# SCH_Type-c-Hub_2024-10-24.net
KiCad netlist of a schematic drawn in EasyEDA
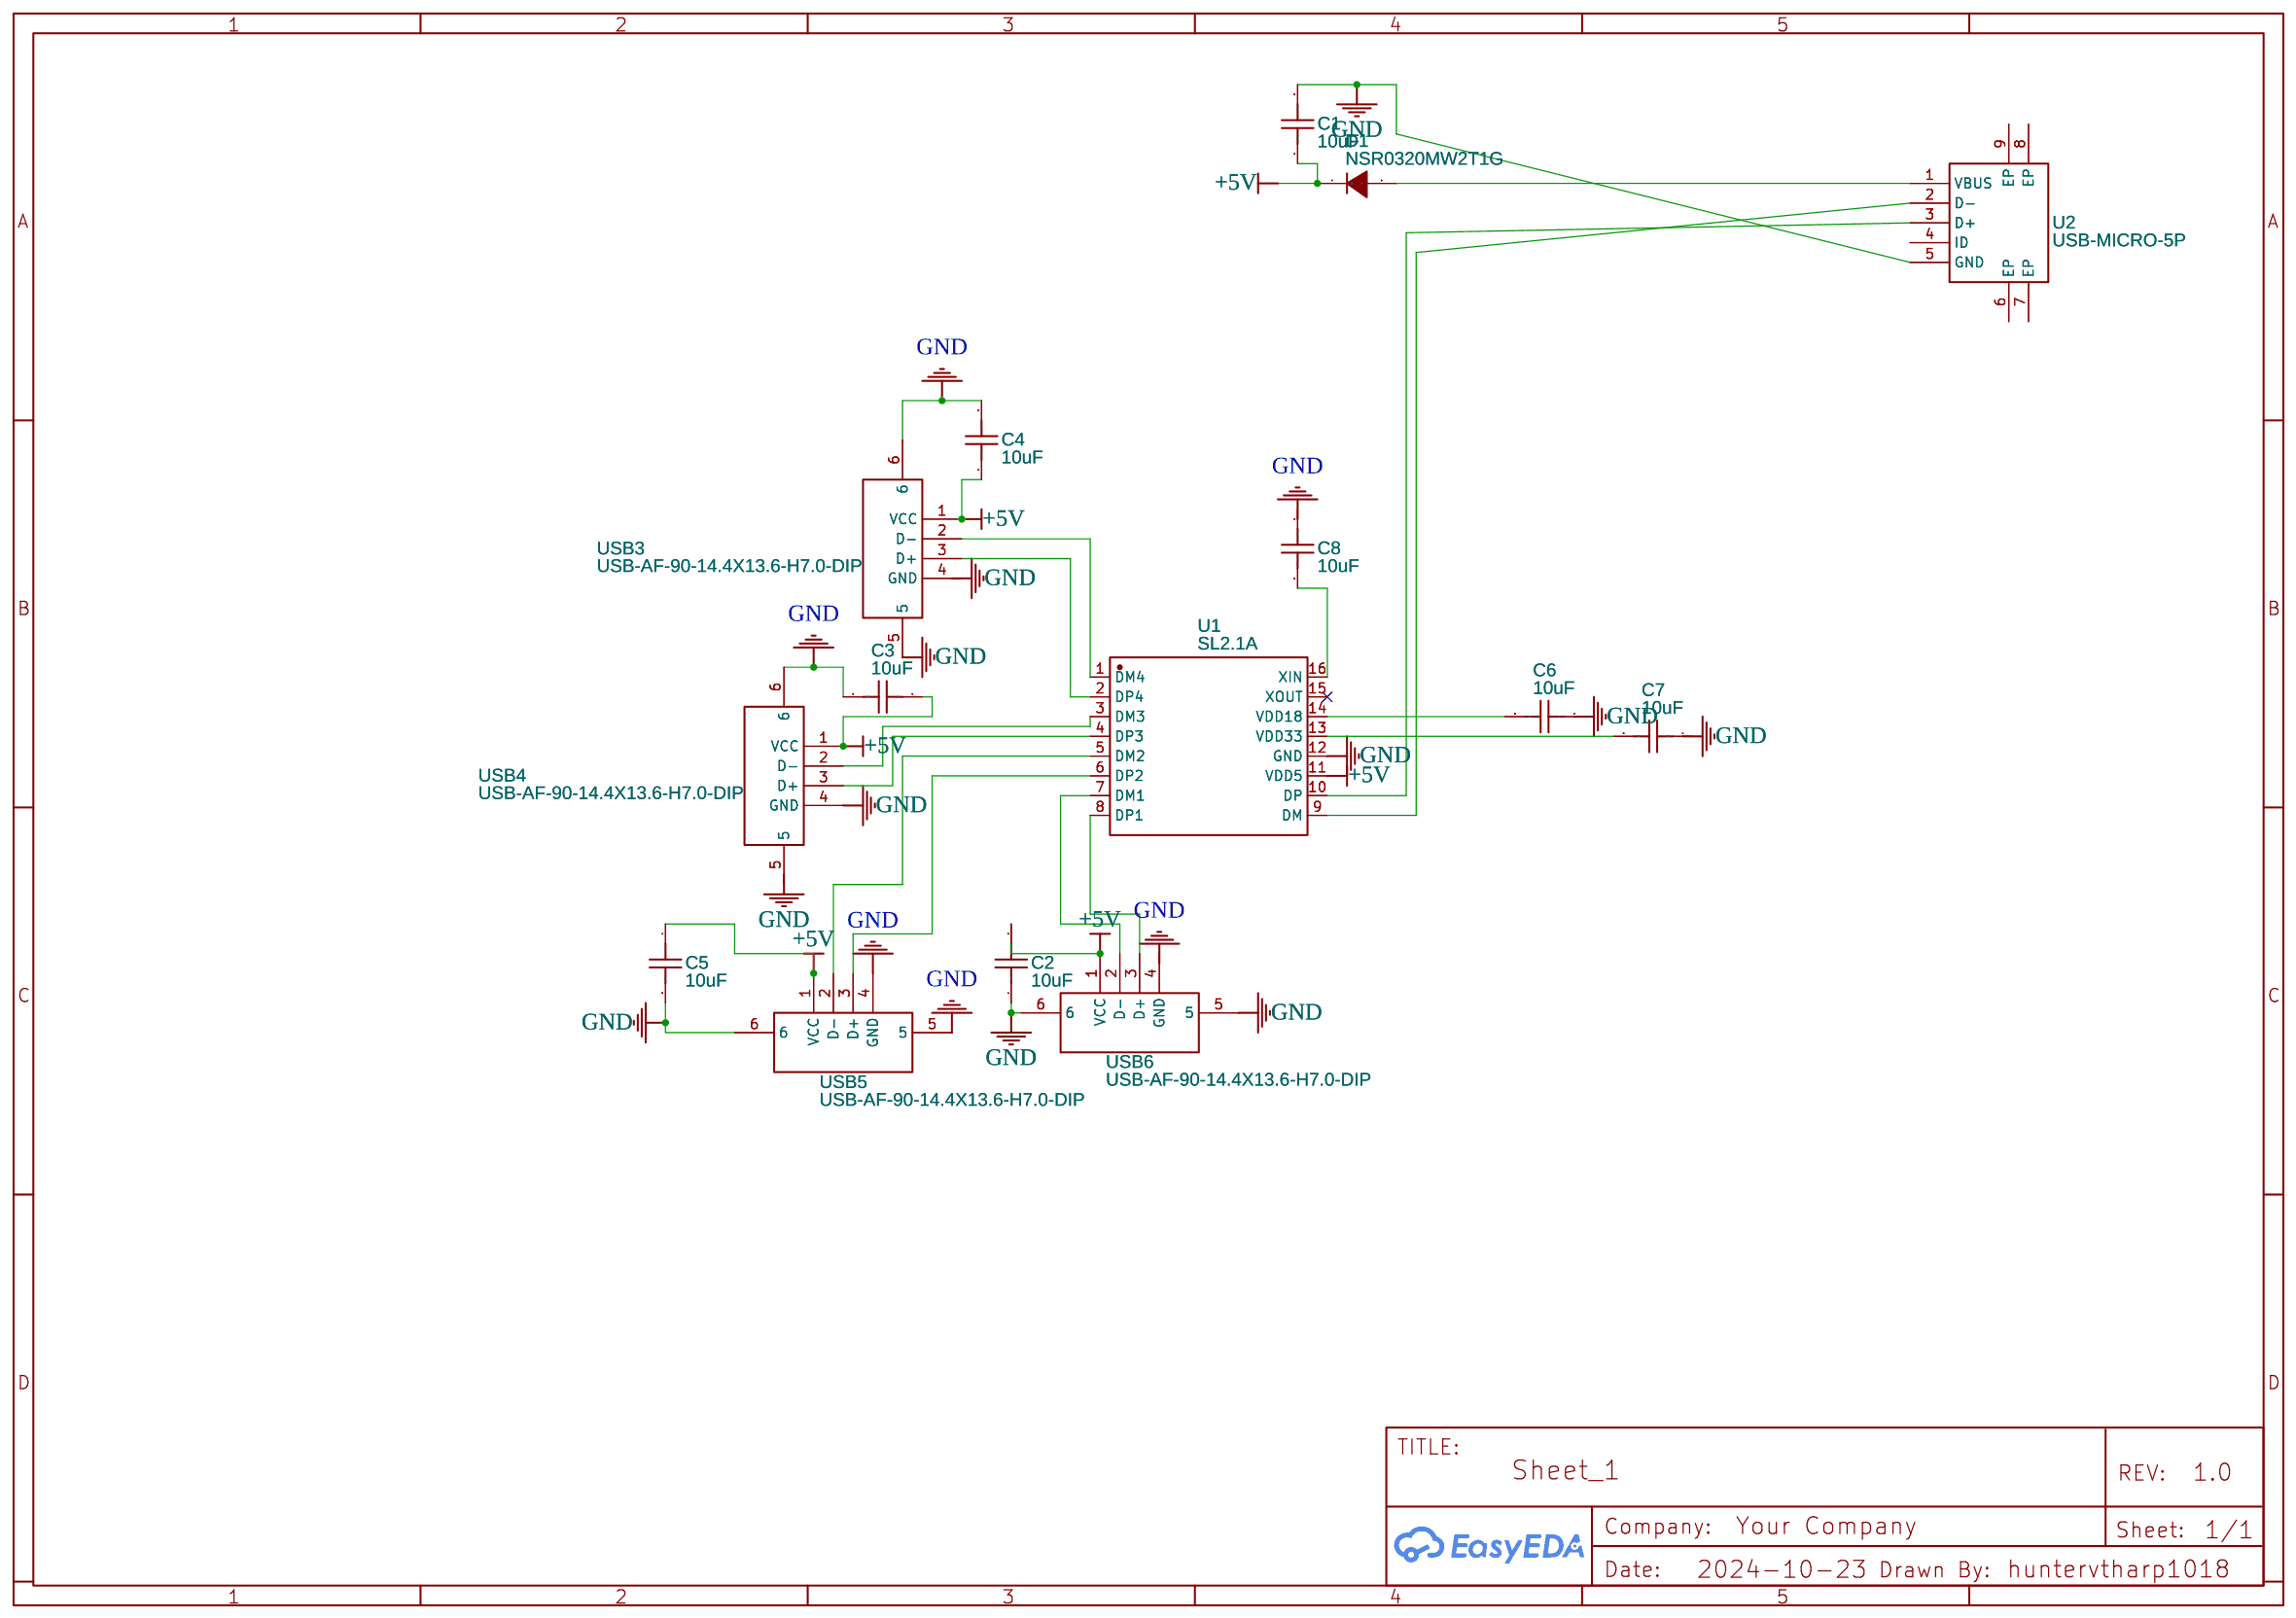
[diagram p0: schematic sheet]

(export (version "E")
  (design (tool "Eeschema 10.0.6"))
  (components
    (comp (ref "C1")
      (value "10uF")
      (fields
        (field (name "Manufacturer Part") "CL10A106KP8NNNC")
        (field (name "Manufacturer") "SAMSUNG(三星)")
      )
      (libsource (lib "") (part "CL10A106KP8NNNC_1"))
    )
    (comp (ref "C2")
      (value "10uF")
      (fields
        (field (name "Manufacturer Part") "CL10A106KP8NNNC")
        (field (name "Manufacturer") "SAMSUNG(三星)")
      )
      (libsource (lib "") (part "CL10A106KP8NNNC_1"))
    )
    (comp (ref "C3")
      (value "10uF")
      (fields
        (field (name "Manufacturer Part") "CL10A106KP8NNNC")
        (field (name "Manufacturer") "SAMSUNG(三星)")
      )
      (libsource (lib "") (part "CL10A106KP8NNNC_2"))
    )
    (comp (ref "C4")
      (value "10uF")
      (fields
        (field (name "Manufacturer Part") "CL10A106KP8NNNC")
        (field (name "Manufacturer") "SAMSUNG(三星)")
      )
      (libsource (lib "") (part "CL10A106KP8NNNC_1"))
    )
    (comp (ref "C5")
      (value "10uF")
      (fields
        (field (name "Manufacturer Part") "CL10A106KP8NNNC")
        (field (name "Manufacturer") "SAMSUNG(三星)")
      )
      (libsource (lib "") (part "CL10A106KP8NNNC"))
    )
    (comp (ref "C6")
      (value "10uF")
      (fields
        (field (name "Manufacturer Part") "CL10A106KP8NNNC")
        (field (name "Manufacturer") "SAMSUNG(三星)")
      )
      (libsource (lib "") (part "CL10A106KP8NNNC_2"))
    )
    (comp (ref "C7")
      (value "10uF")
      (fields
        (field (name "Manufacturer Part") "CL10A106KP8NNNC")
        (field (name "Manufacturer") "SAMSUNG(三星)")
      )
      (libsource (lib "") (part "CL10A106KP8NNNC_2"))
    )
    (comp (ref "C8")
      (value "10uF")
      (fields
        (field (name "Manufacturer Part") "CL10A106KP8NNNC")
        (field (name "Manufacturer") "SAMSUNG(三星)")
      )
      (libsource (lib "") (part "CL10A106KP8NNNC"))
    )
    (comp (ref "D1")
      (value "NSR0320MW2T1G")
      (fields (field (name "Manufacturer") "onsemi(安森美)"))
      (libsource (lib "") (part "NSR0320MW2T1G"))
    )
    (comp (ref "U1")
      (value "SL2.1A")
      (fields (field (name "Manufacturer") "CoreChips(和芯润德)"))
      (libsource (lib "") (part "SL2.1A"))
    )
    (comp (ref "U2")
      (value "USB-MICRO-5P")
      (fields (field (name "Manufacturer Part") "USB-Micro-5P"))
      (libsource (lib "") (part "USB-MICRO-5P"))
    )
    (comp (ref "USB3")
      (value "USB-AF-90-14.4X13.6-H7.0-DIP")
      (fields (field (name "Manufacturer Part") "903-131A1011D10100") (field (name "Manufacturer") "精拓金"))
      (libsource (lib "") (part "USB-AF-90-14.4X13.6-H7.0-DIP_1"))
    )
    (comp (ref "USB4")
      (value "USB-AF-90-14.4X13.6-H7.0-DIP")
      (fields (field (name "Manufacturer Part") "903-131A1011D10100") (field (name "Manufacturer") "精拓金"))
      (libsource (lib "") (part "USB-AF-90-14.4X13.6-H7.0-DIP_1"))
    )
    (comp (ref "USB5")
      (value "USB-AF-90-14.4X13.6-H7.0-DIP")
      (fields (field (name "Manufacturer Part") "903-131A1011D10100") (field (name "Manufacturer") "精拓金"))
      (libsource (lib "") (part "USB-AF-90-14.4X13.6-H7.0-DIP"))
    )
    (comp (ref "USB6")
      (value "USB-AF-90-14.4X13.6-H7.0-DIP")
      (fields (field (name "Manufacturer Part") "903-131A1011D10100") (field (name "Manufacturer") "精拓金"))
      (libsource (lib "") (part "USB-AF-90-14.4X13.6-H7.0-DIP"))
    )
  )
  (nets
    (net (code "1") (name "+5V") (class "Default")
      (node (ref "C1") (pin "1") (pinfunction "1_1") (pintype "unspecified"))
      (node (ref "C2") (pin "2") (pinfunction "2_2") (pintype "unspecified"))
      (node (ref "C3") (pin "1") (pinfunction "1_1") (pintype "unspecified"))
      (node (ref "C4") (pin "1") (pinfunction "1_1") (pintype "unspecified"))
      (node (ref "C5") (pin "1") (pinfunction "1_1") (pintype "unspecified"))
      (node (ref "D1") (pin "1") (pinfunction "C_1") (pintype "unspecified"))
      (node (ref "U1") (pin "11") (pinfunction "VDD5_11") (pintype "unspecified"))
      (node (ref "USB3") (pin "1") (pinfunction "VCC_1") (pintype "unspecified"))
      (node (ref "USB4") (pin "1") (pinfunction "VCC_1") (pintype "unspecified"))
      (node (ref "USB5") (pin "1") (pinfunction "VCC_1") (pintype "unspecified"))
      (node (ref "USB6") (pin "1") (pinfunction "VCC_1") (pintype "unspecified"))
    )
    (net (code "2") (name "GND") (class "Default")
      (node (ref "C1") (pin "2") (pinfunction "2_2") (pintype "unspecified"))
      (node (ref "C2") (pin "1") (pinfunction "1_1") (pintype "unspecified"))
      (node (ref "C3") (pin "2") (pinfunction "2_2") (pintype "unspecified"))
      (node (ref "C4") (pin "2") (pinfunction "2_2") (pintype "unspecified"))
      (node (ref "C5") (pin "2") (pinfunction "2_2") (pintype "unspecified"))
      (node (ref "U1") (pin "12") (pinfunction "GND_12") (pintype "unspecified"))
      (node (ref "U2") (pin "5") (pinfunction "GND_5") (pintype "unspecified"))
      (node (ref "USB3") (pin "5") (pinfunction "5_5") (pintype "unspecified"))
      (node (ref "USB3") (pin "6") (pinfunction "6_6") (pintype "unspecified"))
      (node (ref "USB4") (pin "4") (pinfunction "GND_4") (pintype "unspecified"))
      (node (ref "USB4") (pin "6") (pinfunction "6_6") (pintype "unspecified"))
      (node (ref "USB5") (pin "4") (pinfunction "GND_4") (pintype "unspecified"))
      (node (ref "USB5") (pin "5") (pinfunction "5_5") (pintype "unspecified"))
      (node (ref "USB5") (pin "6") (pinfunction "6_6") (pintype "unspecified"))
      (node (ref "USB6") (pin "5") (pinfunction "5_5") (pintype "unspecified"))
      (node (ref "USB6") (pin "6") (pinfunction "6_6") (pintype "unspecified"))
    )
    (net (code "3") (name "Net-(D1-A)") (class "Default")
      (node (ref "D1") (pin "2") (pinfunction "A_2") (pintype "unspecified"))
      (node (ref "U2") (pin "1") (pinfunction "VBUS_1") (pintype "unspecified"))
    )
    (net (code "4") (name "Net-(U1-DM)") (class "Default")
      (node (ref "U1") (pin "9") (pinfunction "DM_9") (pintype "unspecified"))
      (node (ref "U2") (pin "2") (pinfunction "D-_2") (pintype "unspecified"))
    )
    (net (code "5") (name "Net-(U1-DM1)") (class "Default")
      (node (ref "U1") (pin "7") (pinfunction "DM1_7") (pintype "unspecified"))
      (node (ref "USB6") (pin "2") (pinfunction "D-_2") (pintype "unspecified"))
    )
    (net (code "6") (name "Net-(U1-DM2)") (class "Default")
      (node (ref "U1") (pin "5") (pinfunction "DM2_5") (pintype "unspecified"))
      (node (ref "USB5") (pin "2") (pinfunction "D-_2") (pintype "unspecified"))
    )
    (net (code "7") (name "Net-(U1-DM3)") (class "Default")
      (node (ref "U1") (pin "3") (pinfunction "DM3_3") (pintype "unspecified"))
      (node (ref "USB4") (pin "2") (pinfunction "D-_2") (pintype "unspecified"))
    )
    (net (code "8") (name "Net-(U1-DM4)") (class "Default")
      (node (ref "U1") (pin "1") (pinfunction "DM4_1") (pintype "unspecified"))
      (node (ref "USB3") (pin "2") (pinfunction "D-_2") (pintype "unspecified"))
    )
    (net (code "9") (name "Net-(U1-DP)") (class "Default")
      (node (ref "U1") (pin "10") (pinfunction "DP_10") (pintype "unspecified"))
      (node (ref "U2") (pin "3") (pinfunction "D+_3") (pintype "unspecified"))
    )
    (net (code "10") (name "Net-(U1-DP1)") (class "Default")
      (node (ref "U1") (pin "8") (pinfunction "DP1_8") (pintype "unspecified"))
      (node (ref "USB6") (pin "3") (pinfunction "D+_3") (pintype "unspecified"))
    )
    (net (code "11") (name "Net-(U1-DP2)") (class "Default")
      (node (ref "U1") (pin "6") (pinfunction "DP2_6") (pintype "unspecified"))
      (node (ref "USB5") (pin "3") (pinfunction "D+_3") (pintype "unspecified"))
    )
    (net (code "12") (name "Net-(U1-DP3)") (class "Default")
      (node (ref "U1") (pin "4") (pinfunction "DP3_4") (pintype "unspecified"))
      (node (ref "USB4") (pin "3") (pinfunction "D+_3") (pintype "unspecified"))
    )
    (net (code "13") (name "Net-(U1-DP4)") (class "Default")
      (node (ref "U1") (pin "2") (pinfunction "DP4_2") (pintype "unspecified"))
      (node (ref "USB3") (pin "3") (pinfunction "D+_3") (pintype "unspecified"))
    )
    (net (code "14") (name "Net-(U1-VDD18)") (class "Default")
      (node (ref "C6") (pin "2") (pinfunction "2_2") (pintype "unspecified"))
      (node (ref "U1") (pin "14") (pinfunction "VDD18_14") (pintype "unspecified"))
    )
    (net (code "15") (name "Net-(U1-VDD33)") (class "Default")
      (node (ref "C7") (pin "2") (pinfunction "2_2") (pintype "unspecified"))
      (node (ref "U1") (pin "13") (pinfunction "VDD33_13") (pintype "unspecified"))
    )
    (net (code "16") (name "Net-(U1-XIN)") (class "Default")
      (node (ref "C8") (pin "2") (pinfunction "2_2") (pintype "unspecified"))
      (node (ref "U1") (pin "16") (pinfunction "XIN_16") (pintype "unspecified"))
    )
    (net (code "17") (name "unconnected-(C6-Pad1)") (class "Default")
      (node (ref "C6") (pin "1") (pinfunction "1_1") (pintype "unspecified"))
    )
    (net (code "18") (name "unconnected-(C7-Pad1)") (class "Default")
      (node (ref "C7") (pin "1") (pinfunction "1_1") (pintype "unspecified"))
    )
    (net (code "19") (name "unconnected-(C8-Pad1)") (class "Default")
      (node (ref "C8") (pin "1") (pinfunction "1_1") (pintype "unspecified"))
    )
    (net (code "20") (name "unconnected-(U1-XOUT-Pad15)") (class "Default")
      (node (ref "U1") (pin "15") (pinfunction "XOUT_15") (pintype "unspecified+no_connect"))
    )
    (net (code "21") (name "unconnected-(U2-EP-Pad6)") (class "Default")
      (node (ref "U2") (pin "6") (pinfunction "EP_6") (pintype "unspecified"))
    )
    (net (code "22") (name "unconnected-(U2-EP-Pad7)") (class "Default")
      (node (ref "U2") (pin "7") (pinfunction "EP_7") (pintype "unspecified"))
    )
    (net (code "23") (name "unconnected-(U2-EP-Pad8)") (class "Default")
      (node (ref "U2") (pin "8") (pinfunction "EP_8") (pintype "unspecified"))
    )
    (net (code "24") (name "unconnected-(U2-EP-Pad9)") (class "Default")
      (node (ref "U2") (pin "9") (pinfunction "EP_9") (pintype "unspecified"))
    )
    (net (code "25") (name "unconnected-(U2-ID-Pad4)") (class "Default")
      (node (ref "U2") (pin "4") (pinfunction "ID_4") (pintype "unspecified"))
    )
    (net (code "26") (name "unconnected-(USB3-GND-Pad4)") (class "Default")
      (node (ref "USB3") (pin "4") (pinfunction "GND_4") (pintype "unspecified"))
    )
    (net (code "27") (name "unconnected-(USB4-Pad5)") (class "Default")
      (node (ref "USB4") (pin "5") (pinfunction "5_5") (pintype "unspecified"))
    )
    (net (code "28") (name "unconnected-(USB6-GND-Pad4)") (class "Default")
      (node (ref "USB6") (pin "4") (pinfunction "GND_4") (pintype "unspecified"))
    )
  )
)
